# Walletv2.net
KiCad netlist of a schematic drawn in EAGLE
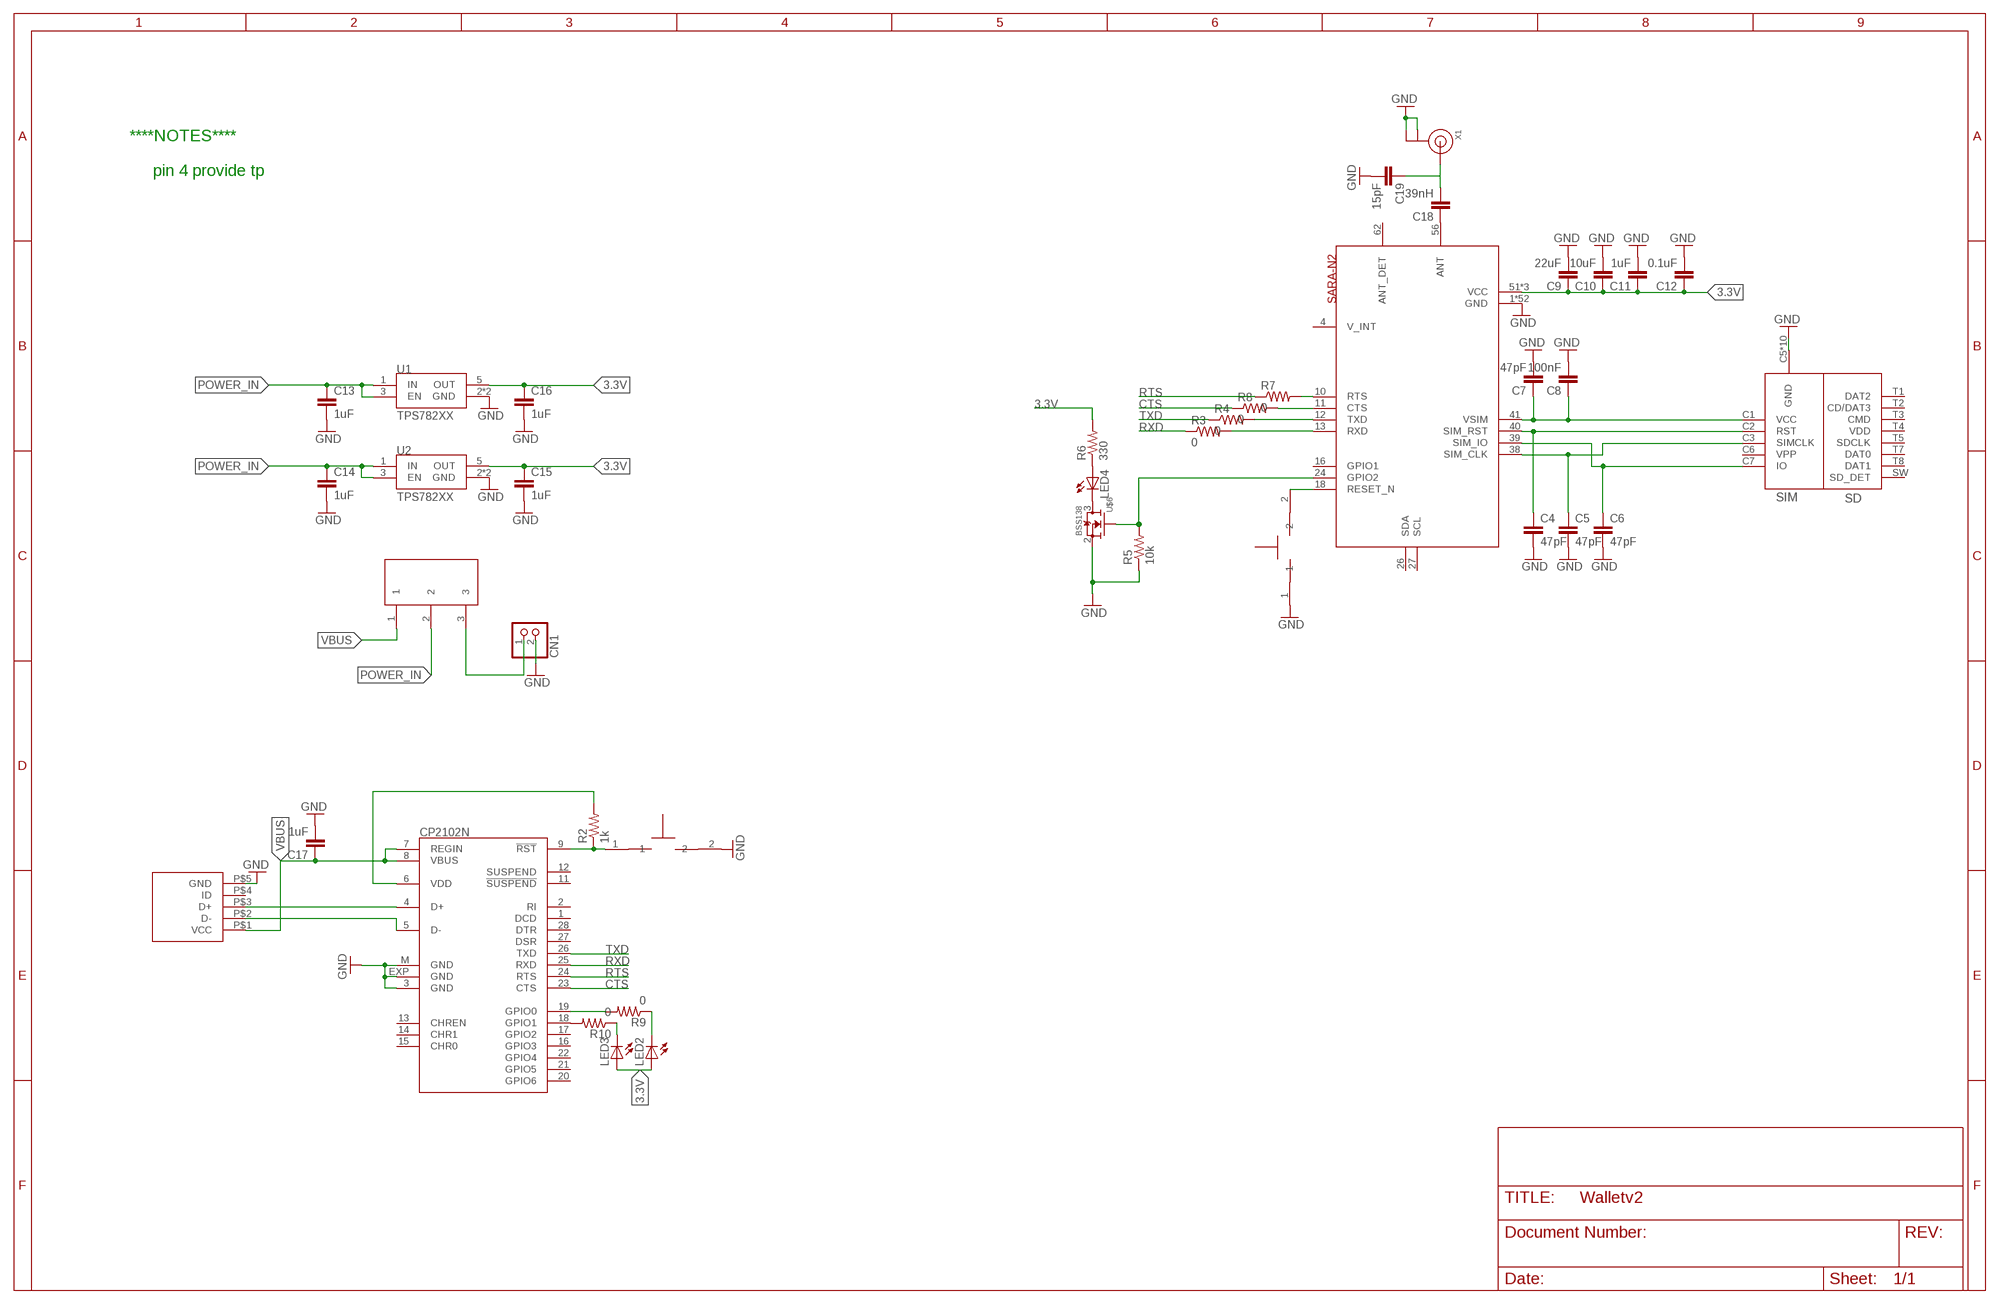
[diagram p0: schematic, sheet 1]

(export (version "E")
  (design (tool "Eeschema 10.0.6"))
  (components
    (comp (ref "C4")
      (value "47pF")
      (footprint "eagle-import:C0402")
      (libsource (lib "eagle-import") (part "C-EUC0402"))
    )
    (comp (ref "C5")
      (value "47pF")
      (footprint "eagle-import:C0402")
      (libsource (lib "eagle-import") (part "C-EUC0402"))
    )
    (comp (ref "C6")
      (value "47pF")
      (footprint "eagle-import:C0402")
      (libsource (lib "eagle-import") (part "C-EUC0402"))
    )
    (comp (ref "C7")
      (value "47pF")
      (footprint "eagle-import:C0402")
      (libsource (lib "eagle-import") (part "C-EUC0402"))
    )
    (comp (ref "C8")
      (value "100nF")
      (footprint "eagle-import:C0402")
      (libsource (lib "eagle-import") (part "C-EUC0402"))
    )
    (comp (ref "C9")
      (value "22uF")
      (footprint "eagle-import:C0805")
      (libsource (lib "eagle-import") (part "C-EUC0805"))
    )
    (comp (ref "C10")
      (value "10uF")
      (footprint "eagle-import:C0603")
      (libsource (lib "eagle-import") (part "C-EUC0603"))
    )
    (comp (ref "C11")
      (value "1uF")
      (footprint "eagle-import:C0402")
      (libsource (lib "eagle-import") (part "C-EUC0402"))
    )
    (comp (ref "C12")
      (value "0.1uF")
      (footprint "eagle-import:C0402")
      (libsource (lib "eagle-import") (part "C-EUC0402"))
    )
    (comp (ref "C13")
      (value "1uF")
      (footprint "eagle-import:C0402")
      (libsource (lib "eagle-import") (part "C-EUC0402"))
    )
    (comp (ref "C14")
      (value "1uF")
      (footprint "eagle-import:C0402")
      (libsource (lib "eagle-import") (part "C-EUC0402"))
    )
    (comp (ref "C15")
      (value "1uF")
      (footprint "eagle-import:C0402")
      (libsource (lib "eagle-import") (part "C-EUC0402"))
    )
    (comp (ref "C16")
      (value "1uF")
      (footprint "eagle-import:C0402")
      (libsource (lib "eagle-import") (part "C-EUC0402"))
    )
    (comp (ref "C17")
      (value "1uF")
      (footprint "eagle-import:C0402")
      (libsource (lib "eagle-import") (part "C-EUC0402"))
    )
    (comp (ref "C18")
      (value "39nH")
      (footprint "eagle-import:C0402")
      (libsource (lib "eagle-import") (part "C-EUC0402"))
    )
    (comp (ref "C19")
      (value "15pF")
      (footprint "eagle-import:C0402")
      (libsource (lib "eagle-import") (part "C-EUC0402"))
    )
    (comp (ref "CN1")
      (value "JST_2PIN-SMT-RA")
      (footprint "eagle-import:JST-PH-2-SMT-RA")
      (libsource (lib "eagle-import") (part "JST_2PIN-SMT-RA"))
    )
    (comp (ref "IC1")
      (value "CP2102")
      (footprint "eagle-import:MLP28")
      (fields (field (name "MF") "FARNELL") (field (name "MPN") "CP2102-GM"))
      (libsource (lib "eagle-import") (part "CP2102"))
    )
    (comp (ref "LED2")
      (value "LEDCHIPLED_0603")
      (footprint "eagle-import:CHIPLED_0603")
      (libsource (lib "eagle-import") (part "LEDCHIPLED_0603"))
    )
    (comp (ref "LED3")
      (value "LEDCHIPLED_0603")
      (footprint "eagle-import:CHIPLED_0603")
      (libsource (lib "eagle-import") (part "LEDCHIPLED_0603"))
    )
    (comp (ref "LED4")
      (value "LEDCHIPLED_0603")
      (footprint "eagle-import:CHIPLED_0603")
      (libsource (lib "eagle-import") (part "LEDCHIPLED_0603"))
    )
    (comp (ref "R2")
      (value "1k")
      (footprint "eagle-import:R0402")
      (libsource (lib "eagle-import") (part "R-US_R0402"))
    )
    (comp (ref "R3")
      (value "0")
      (footprint "eagle-import:R0402")
      (libsource (lib "eagle-import") (part "R-US_R0402"))
    )
    (comp (ref "R4")
      (value "0")
      (footprint "eagle-import:R0402")
      (libsource (lib "eagle-import") (part "R-US_R0402"))
    )
    (comp (ref "R5")
      (value "10k")
      (footprint "eagle-import:R0402")
      (libsource (lib "eagle-import") (part "R-US_R0402"))
    )
    (comp (ref "R6")
      (value "330")
      (footprint "eagle-import:R0402")
      (libsource (lib "eagle-import") (part "R-US_R0402"))
    )
    (comp (ref "R7")
      (value "0")
      (footprint "eagle-import:R0402")
      (libsource (lib "eagle-import") (part "R-US_R0402"))
    )
    (comp (ref "R8")
      (value "0")
      (footprint "eagle-import:R0402")
      (libsource (lib "eagle-import") (part "R-US_R0402"))
    )
    (comp (ref "R9")
      (value "0")
      (footprint "eagle-import:R0402")
      (libsource (lib "eagle-import") (part "R-US_R0402"))
    )
    (comp (ref "R10")
      (value "0")
      (footprint "eagle-import:R0402")
      (libsource (lib "eagle-import") (part "R-US_R0402"))
    )
    (comp (ref "S1")
      (value "TACTILE_SKRKA")
      (footprint "eagle-import:TACTILE_SKRKA")
      (libsource (lib "eagle-import") (part "TACTILE_SKRKA"))
    )
    (comp (ref "S2")
      (value "TACTILE_SKRKA")
      (footprint "eagle-import:TACTILE_SKRKA")
      (libsource (lib "eagle-import") (part "TACTILE_SKRKA"))
    )
    (comp (ref "U$1")
      (value "SARA-N2")
      (footprint "eagle-import:SARA-N2")
      (libsource (lib "eagle-import") (part "SARA-N2"))
    )
    (comp (ref "U$2")
      (value "SIM_SD_MOLEX")
      (footprint "eagle-import:SIM_SD_MOLEX")
      (libsource (lib "eagle-import") (part "SIM_SD_MOLEX"))
    )
    (comp (ref "U$4")
      (value "SPDT_THRU")
      (footprint "eagle-import:SPDT_THRU")
      (libsource (lib "eagle-import") (part "SPDT_THRU"))
    )
    (comp (ref "U$5")
      (value "MICRO_USB")
      (footprint "eagle-import:MOLEX_USB")
      (libsource (lib "eagle-import") (part "MICRO_USB"))
    )
    (comp (ref "U$6")
      (value "BSS138")
      (footprint "eagle-import:SOT23-3")
      (libsource (lib "eagle-import") (part "BSS138"))
    )
    (comp (ref "U1")
      (value "TPS782XX")
      (footprint "eagle-import:SOT23-5L")
      (libsource (lib "eagle-import") (part "TPS782XX"))
    )
    (comp (ref "U2")
      (value "TPS782XX")
      (footprint "eagle-import:SOT23-5L")
      (libsource (lib "eagle-import") (part "TPS782XX"))
    )
    (comp (ref "X1")
      (value "ANTENNA_U.FL")
      (footprint "eagle-import:U.FL")
      (libsource (lib "eagle-import") (part "ANTENNA_U.FL"))
    )
  )
  (nets
    (net (code "1") (name "/CTS") (class "Default")
      (node (ref "IC1") (pin "23") (pinfunction "CTS_23") (pintype "input"))
      (node (ref "R8") (pin "1") (pinfunction "1_1") (pintype "passive"))
    )
    (net (code "2") (name "/RTS") (class "Default")
      (node (ref "IC1") (pin "24") (pinfunction "RTS_24") (pintype "output"))
      (node (ref "R7") (pin "1") (pinfunction "1_1") (pintype "passive"))
    )
    (net (code "3") (name "/RXD") (class "Default")
      (node (ref "IC1") (pin "25") (pinfunction "RXD_25") (pintype "input"))
      (node (ref "R3") (pin "1") (pinfunction "1_1") (pintype "passive"))
    )
    (net (code "4") (name "/TXD") (class "Default")
      (node (ref "IC1") (pin "26") (pinfunction "TXD_26") (pintype "output"))
      (node (ref "R4") (pin "1") (pinfunction "1_1") (pintype "passive"))
    )
    (net (code "5") (name "3.3V") (class "Default")
      (node (ref "C10") (pin "1") (pinfunction "1_1") (pintype "passive"))
      (node (ref "C11") (pin "1") (pinfunction "1_1") (pintype "passive"))
      (node (ref "C12") (pin "1") (pinfunction "1_1") (pintype "passive"))
      (node (ref "C15") (pin "1") (pinfunction "1_1") (pintype "passive"))
      (node (ref "C16") (pin "1") (pinfunction "1_1") (pintype "passive"))
      (node (ref "C9") (pin "1") (pinfunction "1_1") (pintype "passive"))
      (node (ref "LED2") (pin "A") (pinfunction "A_A") (pintype "passive"))
      (node (ref "LED3") (pin "A") (pinfunction "A_A") (pintype "passive"))
      (node (ref "R6") (pin "2") (pinfunction "2_2") (pintype "passive"))
      (node (ref "U$1") (pin "51") (pinfunction "VCC_51") (pintype "bidirectional"))
      (node (ref "U$1") (pin "52") (pinfunction "VCC_52") (pintype "bidirectional"))
      (node (ref "U$1") (pin "53") (pinfunction "VCC_53") (pintype "bidirectional"))
      (node (ref "U1") (pin "5") (pinfunction "OUT_5") (pintype "bidirectional"))
      (node (ref "U2") (pin "5") (pinfunction "OUT_5") (pintype "bidirectional"))
    )
    (net (code "6") (name "GND") (class "Default")
      (node (ref "C10") (pin "2") (pinfunction "2_2") (pintype "passive"))
      (node (ref "C11") (pin "2") (pinfunction "2_2") (pintype "passive"))
      (node (ref "C12") (pin "2") (pinfunction "2_2") (pintype "passive"))
      (node (ref "C13") (pin "2") (pinfunction "2_2") (pintype "passive"))
      (node (ref "C14") (pin "2") (pinfunction "2_2") (pintype "passive"))
      (node (ref "C15") (pin "2") (pinfunction "2_2") (pintype "passive"))
      (node (ref "C16") (pin "2") (pinfunction "2_2") (pintype "passive"))
      (node (ref "C17") (pin "2") (pinfunction "2_2") (pintype "passive"))
      (node (ref "C19") (pin "2") (pinfunction "2_2") (pintype "passive"))
      (node (ref "C4") (pin "2") (pinfunction "2_2") (pintype "passive"))
      (node (ref "C5") (pin "2") (pinfunction "2_2") (pintype "passive"))
      (node (ref "C6") (pin "2") (pinfunction "2_2") (pintype "passive"))
      (node (ref "C7") (pin "2") (pinfunction "2_2") (pintype "passive"))
      (node (ref "C8") (pin "2") (pinfunction "2_2") (pintype "passive"))
      (node (ref "C9") (pin "2") (pinfunction "2_2") (pintype "passive"))
      (node (ref "CN1") (pin "2") (pinfunction "1_2") (pintype "passive"))
      (node (ref "IC1") (pin "3") (pinfunction "GND_3") (pintype "power_in"))
      (node (ref "IC1") (pin "EXP") (pinfunction "GND_EXP") (pintype "power_in"))
      (node (ref "IC1") (pin "M") (pinfunction "GND_M") (pintype "power_in"))
      (node (ref "R5") (pin "1") (pinfunction "1_1") (pintype "passive"))
      (node (ref "S1") (pin "2") (pinfunction "2_2") (pintype "bidirectional"))
      (node (ref "S2") (pin "1") (pinfunction "1_1") (pintype "bidirectional"))
      (node (ref "U$1") (pin "1") (pinfunction "GND_1") (pintype "bidirectional"))
      (node (ref "U$1") (pin "14") (pinfunction "GND_14") (pintype "bidirectional"))
      (node (ref "U$1") (pin "20") (pinfunction "GND_20") (pintype "bidirectional"))
      (node (ref "U$1") (pin "21") (pinfunction "GND_21") (pintype "bidirectional"))
      (node (ref "U$1") (pin "22") (pinfunction "GND_22") (pintype "bidirectional"))
      (node (ref "U$1") (pin "3") (pinfunction "GND_3") (pintype "bidirectional"))
      (node (ref "U$1") (pin "30") (pinfunction "GND_30") (pintype "bidirectional"))
      (node (ref "U$1") (pin "32") (pinfunction "GND_32") (pintype "bidirectional"))
      (node (ref "U$1") (pin "43") (pinfunction "GND_43") (pintype "bidirectional"))
      (node (ref "U$1") (pin "5") (pinfunction "GND_5") (pintype "bidirectional"))
      (node (ref "U$1") (pin "50") (pinfunction "GND_50") (pintype "bidirectional"))
      (node (ref "U$1") (pin "54") (pinfunction "GND_54") (pintype "bidirectional"))
      (node (ref "U$1") (pin "55") (pinfunction "GND_55") (pintype "bidirectional"))
      (node (ref "U$1") (pin "57") (pinfunction "GND_57") (pintype "bidirectional"))
      (node (ref "U$1") (pin "58") (pinfunction "GND_58") (pintype "bidirectional"))
      (node (ref "U$1") (pin "59") (pinfunction "GND_59") (pintype "bidirectional"))
      (node (ref "U$1") (pin "60") (pinfunction "GND_60") (pintype "bidirectional"))
      (node (ref "U$1") (pin "61") (pinfunction "GND_61") (pintype "bidirectional"))
      (node (ref "U$1") (pin "63") (pinfunction "GND_63") (pintype "bidirectional"))
      (node (ref "U$1") (pin "64") (pinfunction "GND_64") (pintype "bidirectional"))
      (node (ref "U$1") (pin "65") (pinfunction "GND_65") (pintype "bidirectional"))
      (node (ref "U$1") (pin "66") (pinfunction "GND_66") (pintype "bidirectional"))
      (node (ref "U$1") (pin "67") (pinfunction "GND_67") (pintype "bidirectional"))
      (node (ref "U$1") (pin "68") (pinfunction "GND_68") (pintype "bidirectional"))
      (node (ref "U$1") (pin "69") (pinfunction "GND_69") (pintype "bidirectional"))
      (node (ref "U$1") (pin "70") (pinfunction "GND_70") (pintype "bidirectional"))
      (node (ref "U$1") (pin "71") (pinfunction "GND_71") (pintype "bidirectional"))
      (node (ref "U$1") (pin "72") (pinfunction "GND_72") (pintype "bidirectional"))
      (node (ref "U$1") (pin "73") (pinfunction "GND_73") (pintype "bidirectional"))
      (node (ref "U$1") (pin "74") (pinfunction "GND_74") (pintype "bidirectional"))
      (node (ref "U$1") (pin "75") (pinfunction "GND_75") (pintype "bidirectional"))
      (node (ref "U$1") (pin "76") (pinfunction "GND_76") (pintype "bidirectional"))
      (node (ref "U$1") (pin "77") (pinfunction "GND_77") (pintype "bidirectional"))
      (node (ref "U$1") (pin "78") (pinfunction "GND_78") (pintype "bidirectional"))
      (node (ref "U$1") (pin "79") (pinfunction "GND_79") (pintype "bidirectional"))
      (node (ref "U$1") (pin "80") (pinfunction "GND_80") (pintype "bidirectional"))
      (node (ref "U$1") (pin "81") (pinfunction "GND_81") (pintype "bidirectional"))
      (node (ref "U$1") (pin "82") (pinfunction "GND_82") (pintype "bidirectional"))
      (node (ref "U$1") (pin "83") (pinfunction "GND_83") (pintype "bidirectional"))
      (node (ref "U$1") (pin "84") (pinfunction "GND_84") (pintype "bidirectional"))
      (node (ref "U$1") (pin "85") (pinfunction "GND_85") (pintype "bidirectional"))
      (node (ref "U$1") (pin "86") (pinfunction "GND_86") (pintype "bidirectional"))
      (node (ref "U$1") (pin "87") (pinfunction "GND_87") (pintype "bidirectional"))
      (node (ref "U$1") (pin "88") (pinfunction "GND_88") (pintype "bidirectional"))
      (node (ref "U$1") (pin "89") (pinfunction "GND_89") (pintype "bidirectional"))
      (node (ref "U$1") (pin "90") (pinfunction "GND_90") (pintype "bidirectional"))
      (node (ref "U$1") (pin "91") (pinfunction "GND_91") (pintype "bidirectional"))
      (node (ref "U$1") (pin "92") (pinfunction "GND_92") (pintype "bidirectional"))
      (node (ref "U$1") (pin "93") (pinfunction "GND_93") (pintype "bidirectional"))
      (node (ref "U$1") (pin "94") (pinfunction "GND_94") (pintype "bidirectional"))
      (node (ref "U$1") (pin "95") (pinfunction "GND_95") (pintype "bidirectional"))
      (node (ref "U$1") (pin "96") (pinfunction "GND_96") (pintype "bidirectional"))
      (node (ref "U$2") (pin "C5") (pinfunction "GND_C5") (pintype "bidirectional"))
      (node (ref "U$2") (pin "G1") (pinfunction "GND_G1") (pintype "bidirectional"))
      (node (ref "U$2") (pin "G2") (pinfunction "GND_G2") (pintype "bidirectional"))
      (node (ref "U$2") (pin "G3") (pinfunction "GND_G3") (pintype "bidirectional"))
      (node (ref "U$2") (pin "G4") (pinfunction "GND_G4") (pintype "bidirectional"))
      (node (ref "U$2") (pin "G5") (pinfunction "GND_G5") (pintype "bidirectional"))
      (node (ref "U$2") (pin "G6") (pinfunction "GND_G6") (pintype "bidirectional"))
      (node (ref "U$2") (pin "G7") (pinfunction "GND_G7") (pintype "bidirectional"))
      (node (ref "U$2") (pin "G8") (pinfunction "GND_G8") (pintype "bidirectional"))
      (node (ref "U$2") (pin "T6") (pinfunction "GND_T6") (pintype "bidirectional"))
      (node (ref "U$5") (pin "P$5") (pinfunction "GND_P$5") (pintype "bidirectional"))
      (node (ref "U$6") (pin "2") (pinfunction "S_2") (pintype "bidirectional"))
      (node (ref "U1") (pin "2") (pinfunction "GND_2") (pintype "bidirectional"))
      (node (ref "U1") (pin "4") (pinfunction "GND_4") (pintype "bidirectional"))
      (node (ref "U2") (pin "2") (pinfunction "GND_2") (pintype "bidirectional"))
      (node (ref "U2") (pin "4") (pinfunction "GND_4") (pintype "bidirectional"))
      (node (ref "X1") (pin "1") (pinfunction "GND_1") (pintype "passive"))
      (node (ref "X1") (pin "2") (pinfunction "GND_2") (pintype "passive"))
    )
    (net (code "7") (name "Net-(CN1-2)") (class "Default")
      (node (ref "CN1") (pin "1") (pinfunction "2_1") (pintype "passive"))
      (node (ref "U$4") (pin "3") (pinfunction "3_3") (pintype "bidirectional"))
    )
    (net (code "8") (name "Net-(IC1-D+)") (class "Default")
      (node (ref "IC1") (pin "4") (pinfunction "D+_4") (pintype "bidirectional"))
      (node (ref "U$5") (pin "P$3") (pinfunction "D+_P$3") (pintype "bidirectional"))
    )
    (net (code "9") (name "Net-(IC1-D-)") (class "Default")
      (node (ref "IC1") (pin "5") (pinfunction "D-_5") (pintype "bidirectional"))
      (node (ref "U$5") (pin "P$2") (pinfunction "D-_P$2") (pintype "bidirectional"))
    )
    (net (code "10") (name "Net-(IC1-GPIO0)") (class "Default")
      (node (ref "IC1") (pin "19") (pinfunction "GPIO0_19") (pintype "bidirectional"))
      (node (ref "R9") (pin "2") (pinfunction "2_2") (pintype "passive"))
    )
    (net (code "11") (name "Net-(IC1-GPIO1)") (class "Default")
      (node (ref "IC1") (pin "18") (pinfunction "GPIO1_18") (pintype "bidirectional"))
      (node (ref "R10") (pin "2") (pinfunction "2_2") (pintype "passive"))
    )
    (net (code "12") (name "Net-(IC1-VDD)") (class "Default")
      (node (ref "IC1") (pin "6") (pinfunction "VDD_6") (pintype "power_in"))
      (node (ref "R2") (pin "2") (pinfunction "2_2") (pintype "passive"))
    )
    (net (code "13") (name "Net-(IC1-~{RST})") (class "Default")
      (node (ref "IC1") (pin "9") (pinfunction "~{RST}_9") (pintype "bidirectional"))
      (node (ref "R2") (pin "1") (pinfunction "1_1") (pintype "passive"))
      (node (ref "S1") (pin "1") (pinfunction "1_1") (pintype "bidirectional"))
    )
    (net (code "14") (name "Net-(LED2-PadC)") (class "Default")
      (node (ref "LED2") (pin "C") (pinfunction "C_C") (pintype "passive"))
      (node (ref "R9") (pin "1") (pinfunction "1_1") (pintype "passive"))
    )
    (net (code "15") (name "Net-(LED3-PadC)") (class "Default")
      (node (ref "LED3") (pin "C") (pinfunction "C_C") (pintype "passive"))
      (node (ref "R10") (pin "1") (pinfunction "1_1") (pintype "passive"))
    )
    (net (code "16") (name "Net-(LED4-PadA)") (class "Default")
      (node (ref "LED4") (pin "A") (pinfunction "A_A") (pintype "passive"))
      (node (ref "R6") (pin "1") (pinfunction "1_1") (pintype "passive"))
    )
    (net (code "17") (name "Net-(U$1-ANT)") (class "Default")
      (node (ref "C18") (pin "1") (pinfunction "1_1") (pintype "passive"))
      (node (ref "U$1") (pin "56") (pinfunction "ANT_56") (pintype "bidirectional"))
    )
    (net (code "18") (name "Net-(U$1-CTS)") (class "Default")
      (node (ref "R8") (pin "2") (pinfunction "2_2") (pintype "passive"))
      (node (ref "U$1") (pin "11") (pinfunction "CTS_11") (pintype "bidirectional"))
    )
    (net (code "19") (name "Net-(U$1-GPIO2)") (class "Default")
      (node (ref "R5") (pin "2") (pinfunction "2_2") (pintype "passive"))
      (node (ref "U$1") (pin "24") (pinfunction "GPIO2_24") (pintype "bidirectional"))
      (node (ref "U$6") (pin "1") (pinfunction "G_1") (pintype "bidirectional"))
    )
    (net (code "20") (name "Net-(U$1-RESET_N)") (class "Default")
      (node (ref "S2") (pin "2") (pinfunction "2_2") (pintype "bidirectional"))
      (node (ref "U$1") (pin "18") (pinfunction "RESET_N_18") (pintype "bidirectional"))
    )
    (net (code "21") (name "Net-(U$1-RTS)") (class "Default")
      (node (ref "R7") (pin "2") (pinfunction "2_2") (pintype "passive"))
      (node (ref "U$1") (pin "10") (pinfunction "RTS_10") (pintype "bidirectional"))
    )
    (net (code "22") (name "Net-(U$1-RXD)") (class "Default")
      (node (ref "R3") (pin "2") (pinfunction "2_2") (pintype "passive"))
      (node (ref "U$1") (pin "13") (pinfunction "RXD_13") (pintype "bidirectional"))
    )
    (net (code "23") (name "Net-(U$1-SIM_CLK)") (class "Default")
      (node (ref "C5") (pin "1") (pinfunction "1_1") (pintype "passive"))
      (node (ref "U$1") (pin "38") (pinfunction "SIM_CLK_38") (pintype "bidirectional"))
      (node (ref "U$2") (pin "C3") (pinfunction "SIMCLK_C3") (pintype "bidirectional"))
    )
    (net (code "24") (name "Net-(U$1-SIM_IO)") (class "Default")
      (node (ref "C6") (pin "1") (pinfunction "1_1") (pintype "passive"))
      (node (ref "U$1") (pin "39") (pinfunction "SIM_IO_39") (pintype "bidirectional"))
      (node (ref "U$2") (pin "C7") (pinfunction "IO_C7") (pintype "bidirectional"))
    )
    (net (code "25") (name "Net-(U$1-SIM_RST)") (class "Default")
      (node (ref "C4") (pin "1") (pinfunction "1_1") (pintype "passive"))
      (node (ref "U$1") (pin "40") (pinfunction "SIM_RST_40") (pintype "bidirectional"))
      (node (ref "U$2") (pin "C2") (pinfunction "RST_C2") (pintype "bidirectional"))
    )
    (net (code "26") (name "Net-(U$1-TXD)") (class "Default")
      (node (ref "R4") (pin "2") (pinfunction "2_2") (pintype "passive"))
      (node (ref "U$1") (pin "12") (pinfunction "TXD_12") (pintype "bidirectional"))
    )
    (net (code "27") (name "Net-(U$1-VSIM)") (class "Default")
      (node (ref "C7") (pin "1") (pinfunction "1_1") (pintype "passive"))
      (node (ref "C8") (pin "1") (pinfunction "1_1") (pintype "passive"))
      (node (ref "U$1") (pin "41") (pinfunction "VSIM_41") (pintype "bidirectional"))
      (node (ref "U$2") (pin "C1") (pinfunction "VCC_C1") (pintype "bidirectional"))
    )
    (net (code "28") (name "Net-(U$6-D)") (class "Default")
      (node (ref "LED4") (pin "C") (pinfunction "C_C") (pintype "passive"))
      (node (ref "U$6") (pin "3") (pinfunction "D_3") (pintype "bidirectional"))
    )
    (net (code "29") (name "Net-(X1-SIGNAL)") (class "Default")
      (node (ref "C18") (pin "2") (pinfunction "2_2") (pintype "passive"))
      (node (ref "C19") (pin "1") (pinfunction "1_1") (pintype "passive"))
      (node (ref "X1") (pin "3") (pinfunction "SIGNAL_3") (pintype "passive"))
    )
    (net (code "30") (name "POWER_IN") (class "Default")
      (node (ref "C13") (pin "1") (pinfunction "1_1") (pintype "passive"))
      (node (ref "C14") (pin "1") (pinfunction "1_1") (pintype "passive"))
      (node (ref "U$4") (pin "2") (pinfunction "2_2") (pintype "bidirectional"))
      (node (ref "U1") (pin "1") (pinfunction "IN_1") (pintype "bidirectional"))
      (node (ref "U1") (pin "3") (pinfunction "EN_3") (pintype "bidirectional"))
      (node (ref "U2") (pin "1") (pinfunction "IN_1") (pintype "bidirectional"))
      (node (ref "U2") (pin "3") (pinfunction "EN_3") (pintype "bidirectional"))
    )
    (net (code "31") (name "VBUS") (class "Default")
      (node (ref "C17") (pin "1") (pinfunction "1_1") (pintype "passive"))
      (node (ref "IC1") (pin "7") (pinfunction "REGIN_7") (pintype "passive"))
      (node (ref "IC1") (pin "8") (pinfunction "VBUS_8") (pintype "input"))
      (node (ref "U$4") (pin "1") (pinfunction "1_1") (pintype "bidirectional"))
      (node (ref "U$5") (pin "P$1") (pinfunction "VCC_P$1") (pintype "bidirectional"))
    )
    (net (code "32") (name "unconnected-(IC1-CHR0-Pad15)") (class "Default")
      (node (ref "IC1") (pin "15") (pinfunction "CHR0_15") (pintype "bidirectional"))
    )
    (net (code "33") (name "unconnected-(IC1-CHR1-Pad14)") (class "Default")
      (node (ref "IC1") (pin "14") (pinfunction "CHR1_14") (pintype "bidirectional"))
    )
    (net (code "34") (name "unconnected-(IC1-CHREN-Pad13)") (class "Default")
      (node (ref "IC1") (pin "13") (pinfunction "CHREN_13") (pintype "bidirectional"))
    )
    (net (code "35") (name "unconnected-(IC1-DCD-Pad1)") (class "Default")
      (node (ref "IC1") (pin "1") (pinfunction "DCD_1") (pintype "input"))
    )
    (net (code "36") (name "unconnected-(IC1-DSR-Pad27)") (class "Default")
      (node (ref "IC1") (pin "27") (pinfunction "DSR_27") (pintype "input"))
    )
    (net (code "37") (name "unconnected-(IC1-DTR-Pad28)") (class "Default")
      (node (ref "IC1") (pin "28") (pinfunction "DTR_28") (pintype "output"))
    )
    (net (code "38") (name "unconnected-(IC1-GPIO2-Pad17)") (class "Default")
      (node (ref "IC1") (pin "17") (pinfunction "GPIO2_17") (pintype "bidirectional"))
    )
    (net (code "39") (name "unconnected-(IC1-GPIO3-Pad16)") (class "Default")
      (node (ref "IC1") (pin "16") (pinfunction "GPIO3_16") (pintype "bidirectional"))
    )
    (net (code "40") (name "unconnected-(IC1-GPIO4-Pad22)") (class "Default")
      (node (ref "IC1") (pin "22") (pinfunction "GPIO4_22") (pintype "bidirectional"))
    )
    (net (code "41") (name "unconnected-(IC1-GPIO5-Pad21)") (class "Default")
      (node (ref "IC1") (pin "21") (pinfunction "GPIO5_21") (pintype "bidirectional"))
    )
    (net (code "42") (name "unconnected-(IC1-GPIO6-Pad20)") (class "Default")
      (node (ref "IC1") (pin "20") (pinfunction "GPIO6_20") (pintype "bidirectional"))
    )
    (net (code "43") (name "unconnected-(IC1-RI-Pad2)") (class "Default")
      (node (ref "IC1") (pin "2") (pinfunction "RI_2") (pintype "input"))
    )
    (net (code "44") (name "unconnected-(IC1-SUSPEND-Pad12)") (class "Default")
      (node (ref "IC1") (pin "12") (pinfunction "SUSPEND_12") (pintype "output"))
    )
    (net (code "45") (name "unconnected-(IC1-~{SUSPEND}-Pad11)") (class "Default")
      (node (ref "IC1") (pin "11") (pinfunction "~{SUSPEND}_11") (pintype "output"))
    )
    (net (code "46") (name "unconnected-(U$1-ANT_DET-Pad62)") (class "Default")
      (node (ref "U$1") (pin "62") (pinfunction "ANT_DET_62") (pintype "bidirectional"))
    )
    (net (code "47") (name "unconnected-(U$1-GPIO1-Pad16)") (class "Default")
      (node (ref "U$1") (pin "16") (pinfunction "GPIO1_16") (pintype "bidirectional"))
    )
    (net (code "48") (name "unconnected-(U$1-SCL-Pad27)") (class "Default")
      (node (ref "U$1") (pin "27") (pinfunction "SCL_27") (pintype "bidirectional"))
    )
    (net (code "49") (name "unconnected-(U$1-SDA-Pad26)") (class "Default")
      (node (ref "U$1") (pin "26") (pinfunction "SDA_26") (pintype "bidirectional"))
    )
    (net (code "50") (name "unconnected-(U$1-V_INT-Pad4)") (class "Default")
      (node (ref "U$1") (pin "4") (pinfunction "V_INT_4") (pintype "bidirectional"))
    )
    (net (code "51") (name "unconnected-(U$2-CD{slash}DAT3-PadT2)") (class "Default")
      (node (ref "U$2") (pin "T2") (pinfunction "CD/DAT3_T2") (pintype "bidirectional"))
    )
    (net (code "52") (name "unconnected-(U$2-CMD-PadT3)") (class "Default")
      (node (ref "U$2") (pin "T3") (pinfunction "CMD_T3") (pintype "bidirectional"))
    )
    (net (code "53") (name "unconnected-(U$2-DAT0-PadT7)") (class "Default")
      (node (ref "U$2") (pin "T7") (pinfunction "DAT0_T7") (pintype "bidirectional"))
    )
    (net (code "54") (name "unconnected-(U$2-DAT1-PadT8)") (class "Default")
      (node (ref "U$2") (pin "T8") (pinfunction "DAT1_T8") (pintype "bidirectional"))
    )
    (net (code "55") (name "unconnected-(U$2-DAT2-PadT1)") (class "Default")
      (node (ref "U$2") (pin "T1") (pinfunction "DAT2_T1") (pintype "bidirectional"))
    )
    (net (code "56") (name "unconnected-(U$2-SDCLK-PadT5)") (class "Default")
      (node (ref "U$2") (pin "T5") (pinfunction "SDCLK_T5") (pintype "bidirectional"))
    )
    (net (code "57") (name "unconnected-(U$2-SD_DET-PadSW)") (class "Default")
      (node (ref "U$2") (pin "SW") (pinfunction "SD_DET_SW") (pintype "bidirectional"))
    )
    (net (code "58") (name "unconnected-(U$2-VDD-PadT4)") (class "Default")
      (node (ref "U$2") (pin "T4") (pinfunction "VDD_T4") (pintype "bidirectional"))
    )
    (net (code "59") (name "unconnected-(U$2-VPP-PadC6)") (class "Default")
      (node (ref "U$2") (pin "C6") (pinfunction "VPP_C6") (pintype "bidirectional"))
    )
    (net (code "60") (name "unconnected-(U$5-ID-PadP$4)") (class "Default")
      (node (ref "U$5") (pin "P$4") (pinfunction "ID_P$4") (pintype "bidirectional"))
    )
  )
)
